# VPower_feed.net
KiCad netlist of a schematic drawn in EAGLE
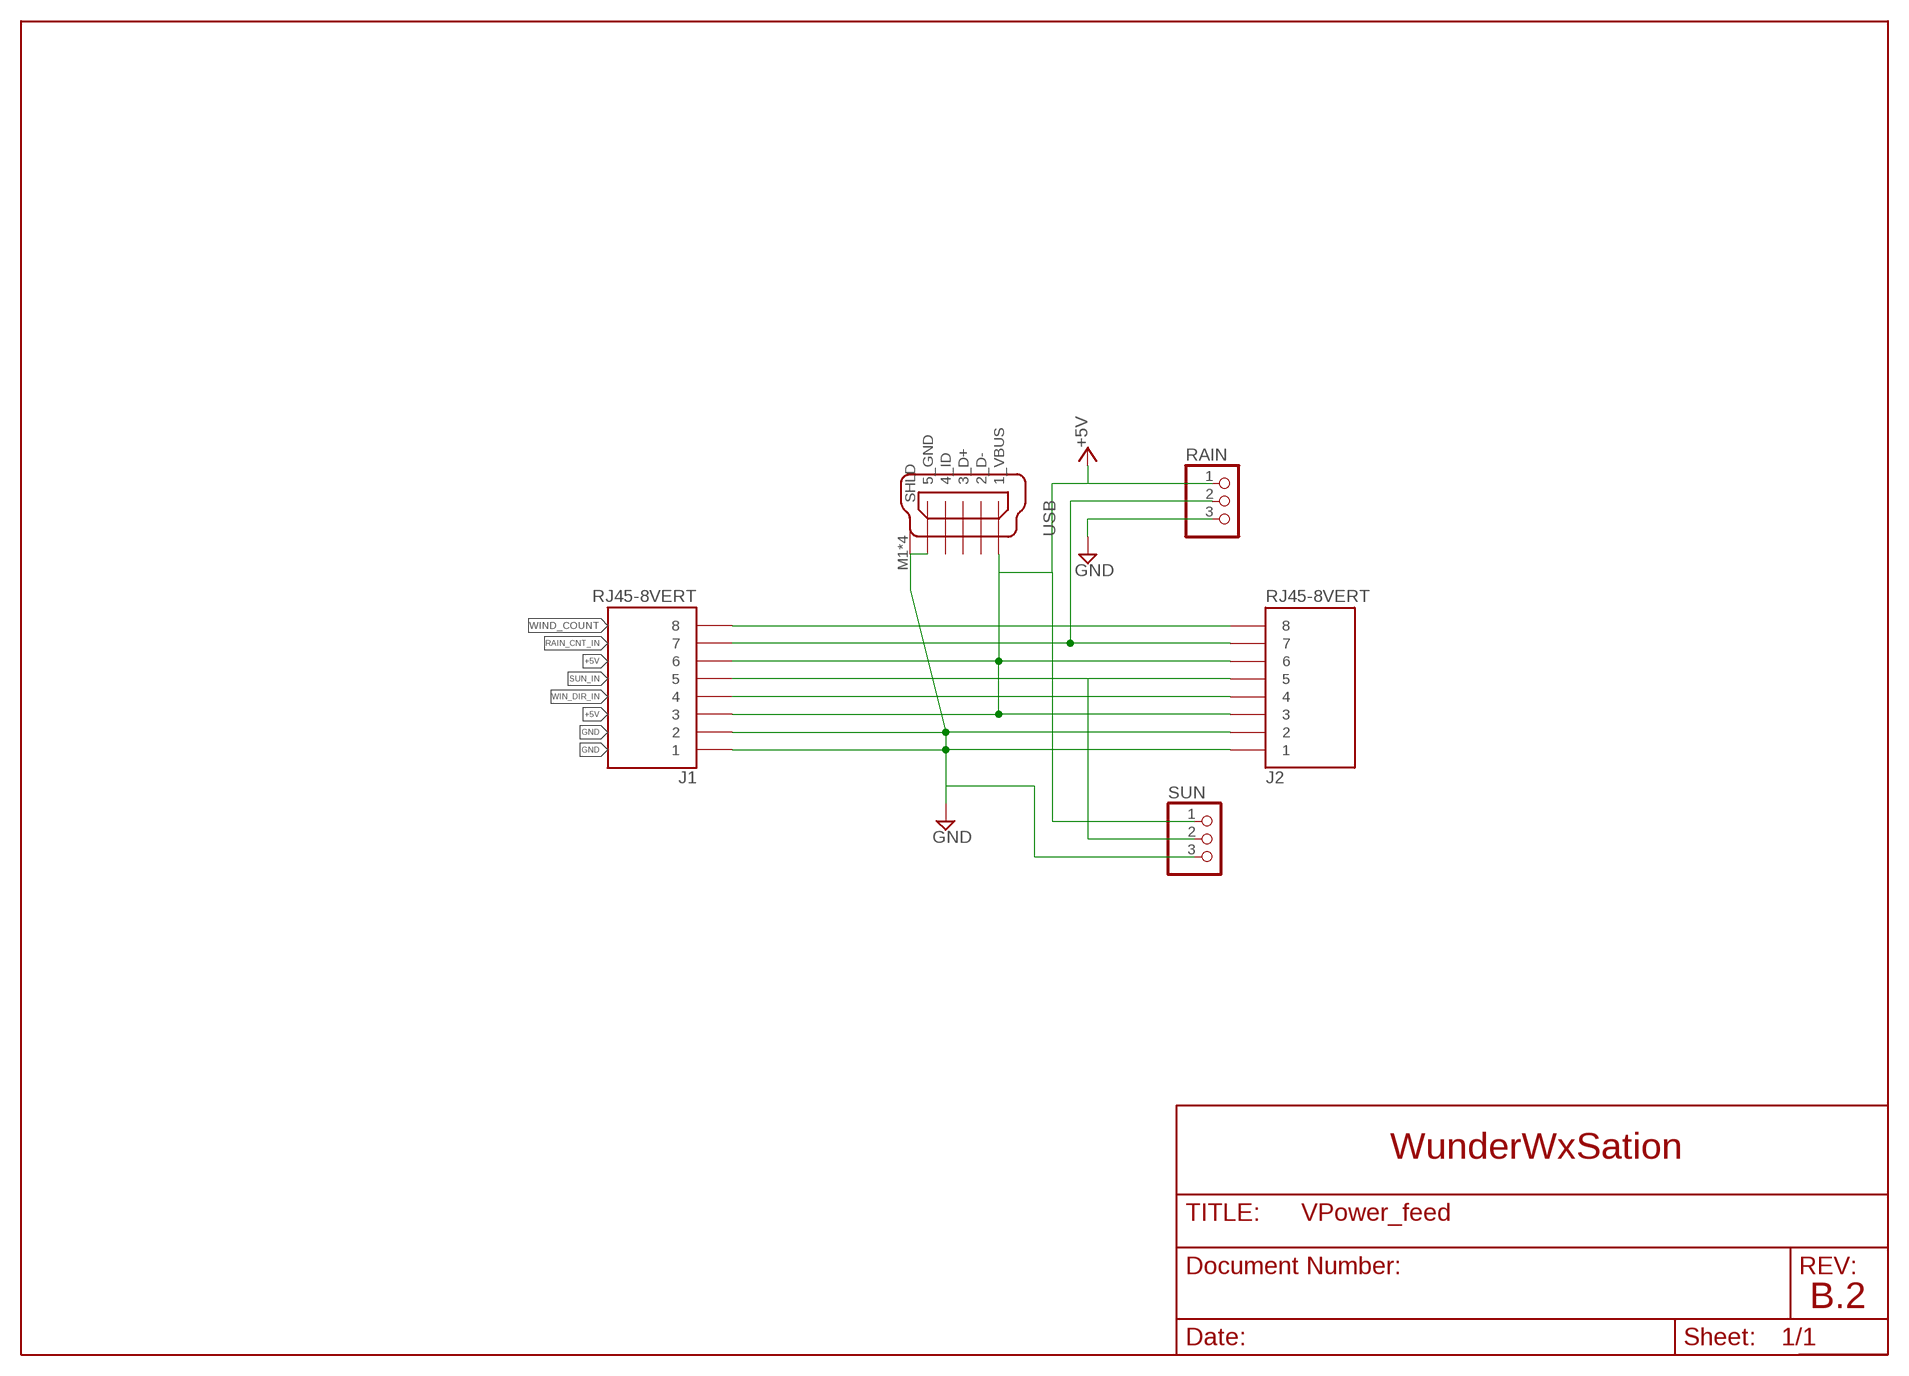
[diagram p0: schematic, sheet 1]

(export (version "E")
  (design (tool "Eeschema 10.0.6"))
  (components
    (comp (ref "J1")
      (value "RJ45-8VERT")
      (footprint "eagle-import:RJ45_VERT")
      (libsource (lib "eagle-import") (part "RJ45-8VERT"))
    )
    (comp (ref "J2")
      (value "RJ45-8VERT")
      (footprint "eagle-import:RJ45_VERT")
      (libsource (lib "eagle-import") (part "RJ45-8VERT"))
    )
    (comp (ref "RAIN")
      (value "PINHD-1X3MOLEX_KK")
      (footprint "eagle-import:1X3_MOLEX_KK")
      (libsource (lib "eagle-import") (part "PINHD-1X3MOLEX_KK"))
    )
    (comp (ref "SUN")
      (value "PINHD-1X3MOLEX_KK")
      (footprint "eagle-import:1X3_MOLEX_KK")
      (libsource (lib "eagle-import") (part "PINHD-1X3MOLEX_KK"))
    )
    (comp (ref "USB")
      (value "MINI-USB-32005-301")
      (footprint "eagle-import:32005-301")
      (libsource (lib "eagle-import") (part "MINI-USB-32005-301"))
    )
  )
  (nets
    (net (code "1") (name "+5V") (class "Default")
      (node (ref "J1") (pin "P$3") (pinfunction "3_P$3") (pintype "bidirectional"))
      (node (ref "J1") (pin "P$6") (pinfunction "6_P$6") (pintype "bidirectional"))
      (node (ref "J2") (pin "P$3") (pinfunction "3_P$3") (pintype "bidirectional"))
      (node (ref "J2") (pin "P$6") (pinfunction "6_P$6") (pintype "bidirectional"))
      (node (ref "RAIN") (pin "1") (pinfunction "1_1") (pintype "passive"))
      (node (ref "SUN") (pin "1") (pinfunction "1_1") (pintype "passive"))
      (node (ref "USB") (pin "1_VBUS") (pinfunction "1_VBUS_1_VBUS") (pintype "passive"))
    )
    (net (code "2") (name "GND") (class "Default")
      (node (ref "J1") (pin "P$1") (pinfunction "1_P$1") (pintype "bidirectional"))
      (node (ref "J1") (pin "P$2") (pinfunction "2_P$2") (pintype "bidirectional"))
      (node (ref "J2") (pin "P$1") (pinfunction "1_P$1") (pintype "bidirectional"))
      (node (ref "J2") (pin "P$2") (pinfunction "2_P$2") (pintype "bidirectional"))
      (node (ref "RAIN") (pin "3") (pinfunction "3_3") (pintype "passive"))
      (node (ref "SUN") (pin "3") (pinfunction "3_3") (pintype "passive"))
      (node (ref "USB") (pin "5_USB_GND") (pinfunction "5_GND_5_USB_GND") (pintype "passive"))
      (node (ref "USB") (pin "M1") (pinfunction "SHLD_M1") (pintype "passive"))
      (node (ref "USB") (pin "M2") (pinfunction "SHLD_M2") (pintype "passive"))
      (node (ref "USB") (pin "M3") (pinfunction "SHLD_M3") (pintype "passive"))
      (node (ref "USB") (pin "M4") (pinfunction "SHLD_M4") (pintype "passive"))
    )
    (net (code "3") (name "RAIN_CNT_IN") (class "Default")
      (node (ref "J1") (pin "P$7") (pinfunction "7_P$7") (pintype "bidirectional"))
      (node (ref "J2") (pin "P$7") (pinfunction "7_P$7") (pintype "bidirectional"))
      (node (ref "RAIN") (pin "2") (pinfunction "2_2") (pintype "passive"))
    )
    (net (code "4") (name "SUN_IN") (class "Default")
      (node (ref "J1") (pin "P$5") (pinfunction "5_P$5") (pintype "bidirectional"))
      (node (ref "J2") (pin "P$5") (pinfunction "5_P$5") (pintype "bidirectional"))
      (node (ref "SUN") (pin "2") (pinfunction "2_2") (pintype "passive"))
    )
    (net (code "5") (name "WIND_COUNT") (class "Default")
      (node (ref "J1") (pin "P$8") (pinfunction "8_P$8") (pintype "bidirectional"))
      (node (ref "J2") (pin "P$8") (pinfunction "8_P$8") (pintype "bidirectional"))
    )
    (net (code "6") (name "WIN_DIR_IN") (class "Default")
      (node (ref "J1") (pin "P$4") (pinfunction "4_P$4") (pintype "bidirectional"))
      (node (ref "J2") (pin "P$4") (pinfunction "4_P$4") (pintype "bidirectional"))
    )
    (net (code "7") (name "unconnected-(USB-Pad2_D-)") (class "Default")
      (node (ref "USB") (pin "2_D-") (pinfunction "2_D-_2_D-") (pintype "passive"))
    )
    (net (code "8") (name "unconnected-(USB-Pad3_D+)") (class "Default")
      (node (ref "USB") (pin "3_D+") (pinfunction "3_D+_3_D+") (pintype "passive"))
    )
    (net (code "9") (name "unconnected-(USB-Pad4_ID)") (class "Default")
      (node (ref "USB") (pin "4_ID") (pinfunction "4_ID_4_ID") (pintype "passive"))
    )
  )
)
